# UART_Output.net
KiCad netlist of a schematic drawn in Altium Designer
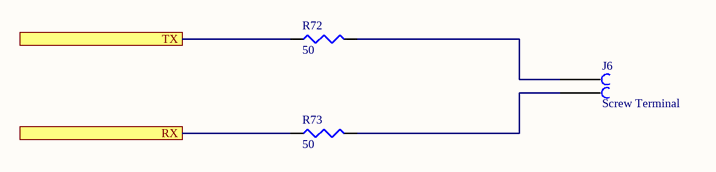
[diagram p0: UART Output.SchDoc]

(export (version "E")
  (design (tool "Eeschema 10.0.6"))
  (components
    (comp (ref "J6")
      (value "Screw Terminal")
      (footprint "Screw Terminal")
      (libsource (lib "AvionicsParts") (part "Screw Terminal"))
    )
    (comp (ref "R72")
      (value "50")
      (footprint "0603 Footprint")
      (description "Resistor")
      (fields (field (name "Comment") "Res3") (field (name "PUBLISHER") "Altium Limited"))
      (libsource (lib "Miscellaneous Devices") (part "Res3"))
    )
    (comp (ref "R73")
      (value "50")
      (footprint "0603 Footprint")
      (description "Resistor")
      (fields (field (name "Comment") "Res3") (field (name "PUBLISHER") "Altium Limited"))
      (libsource (lib "Miscellaneous Devices") (part "Res3"))
    )
  )
  (nets
    (net (code "1") (name "/RX") (class "Default")
      (node (ref "R73") (pin "1") (pinfunction "1_1") (pintype "passive"))
    )
    (net (code "2") (name "/TX") (class "Default")
      (node (ref "R72") (pin "1") (pinfunction "1_1") (pintype "passive"))
    )
    (net (code "3") (name "Net-(J6-Pad1)") (class "Default")
      (node (ref "J6") (pin "1") (pinfunction "1_1") (pintype "passive"))
      (node (ref "R72") (pin "2") (pinfunction "2_2") (pintype "passive"))
    )
    (net (code "4") (name "Net-(J6-Pad2)") (class "Default")
      (node (ref "J6") (pin "2") (pinfunction "2_2") (pintype "passive"))
      (node (ref "R73") (pin "2") (pinfunction "2_2") (pintype "passive"))
    )
  )
)
